# CAMERA_INTERFACE.net
KiCad netlist of a schematic drawn in Altium Designer
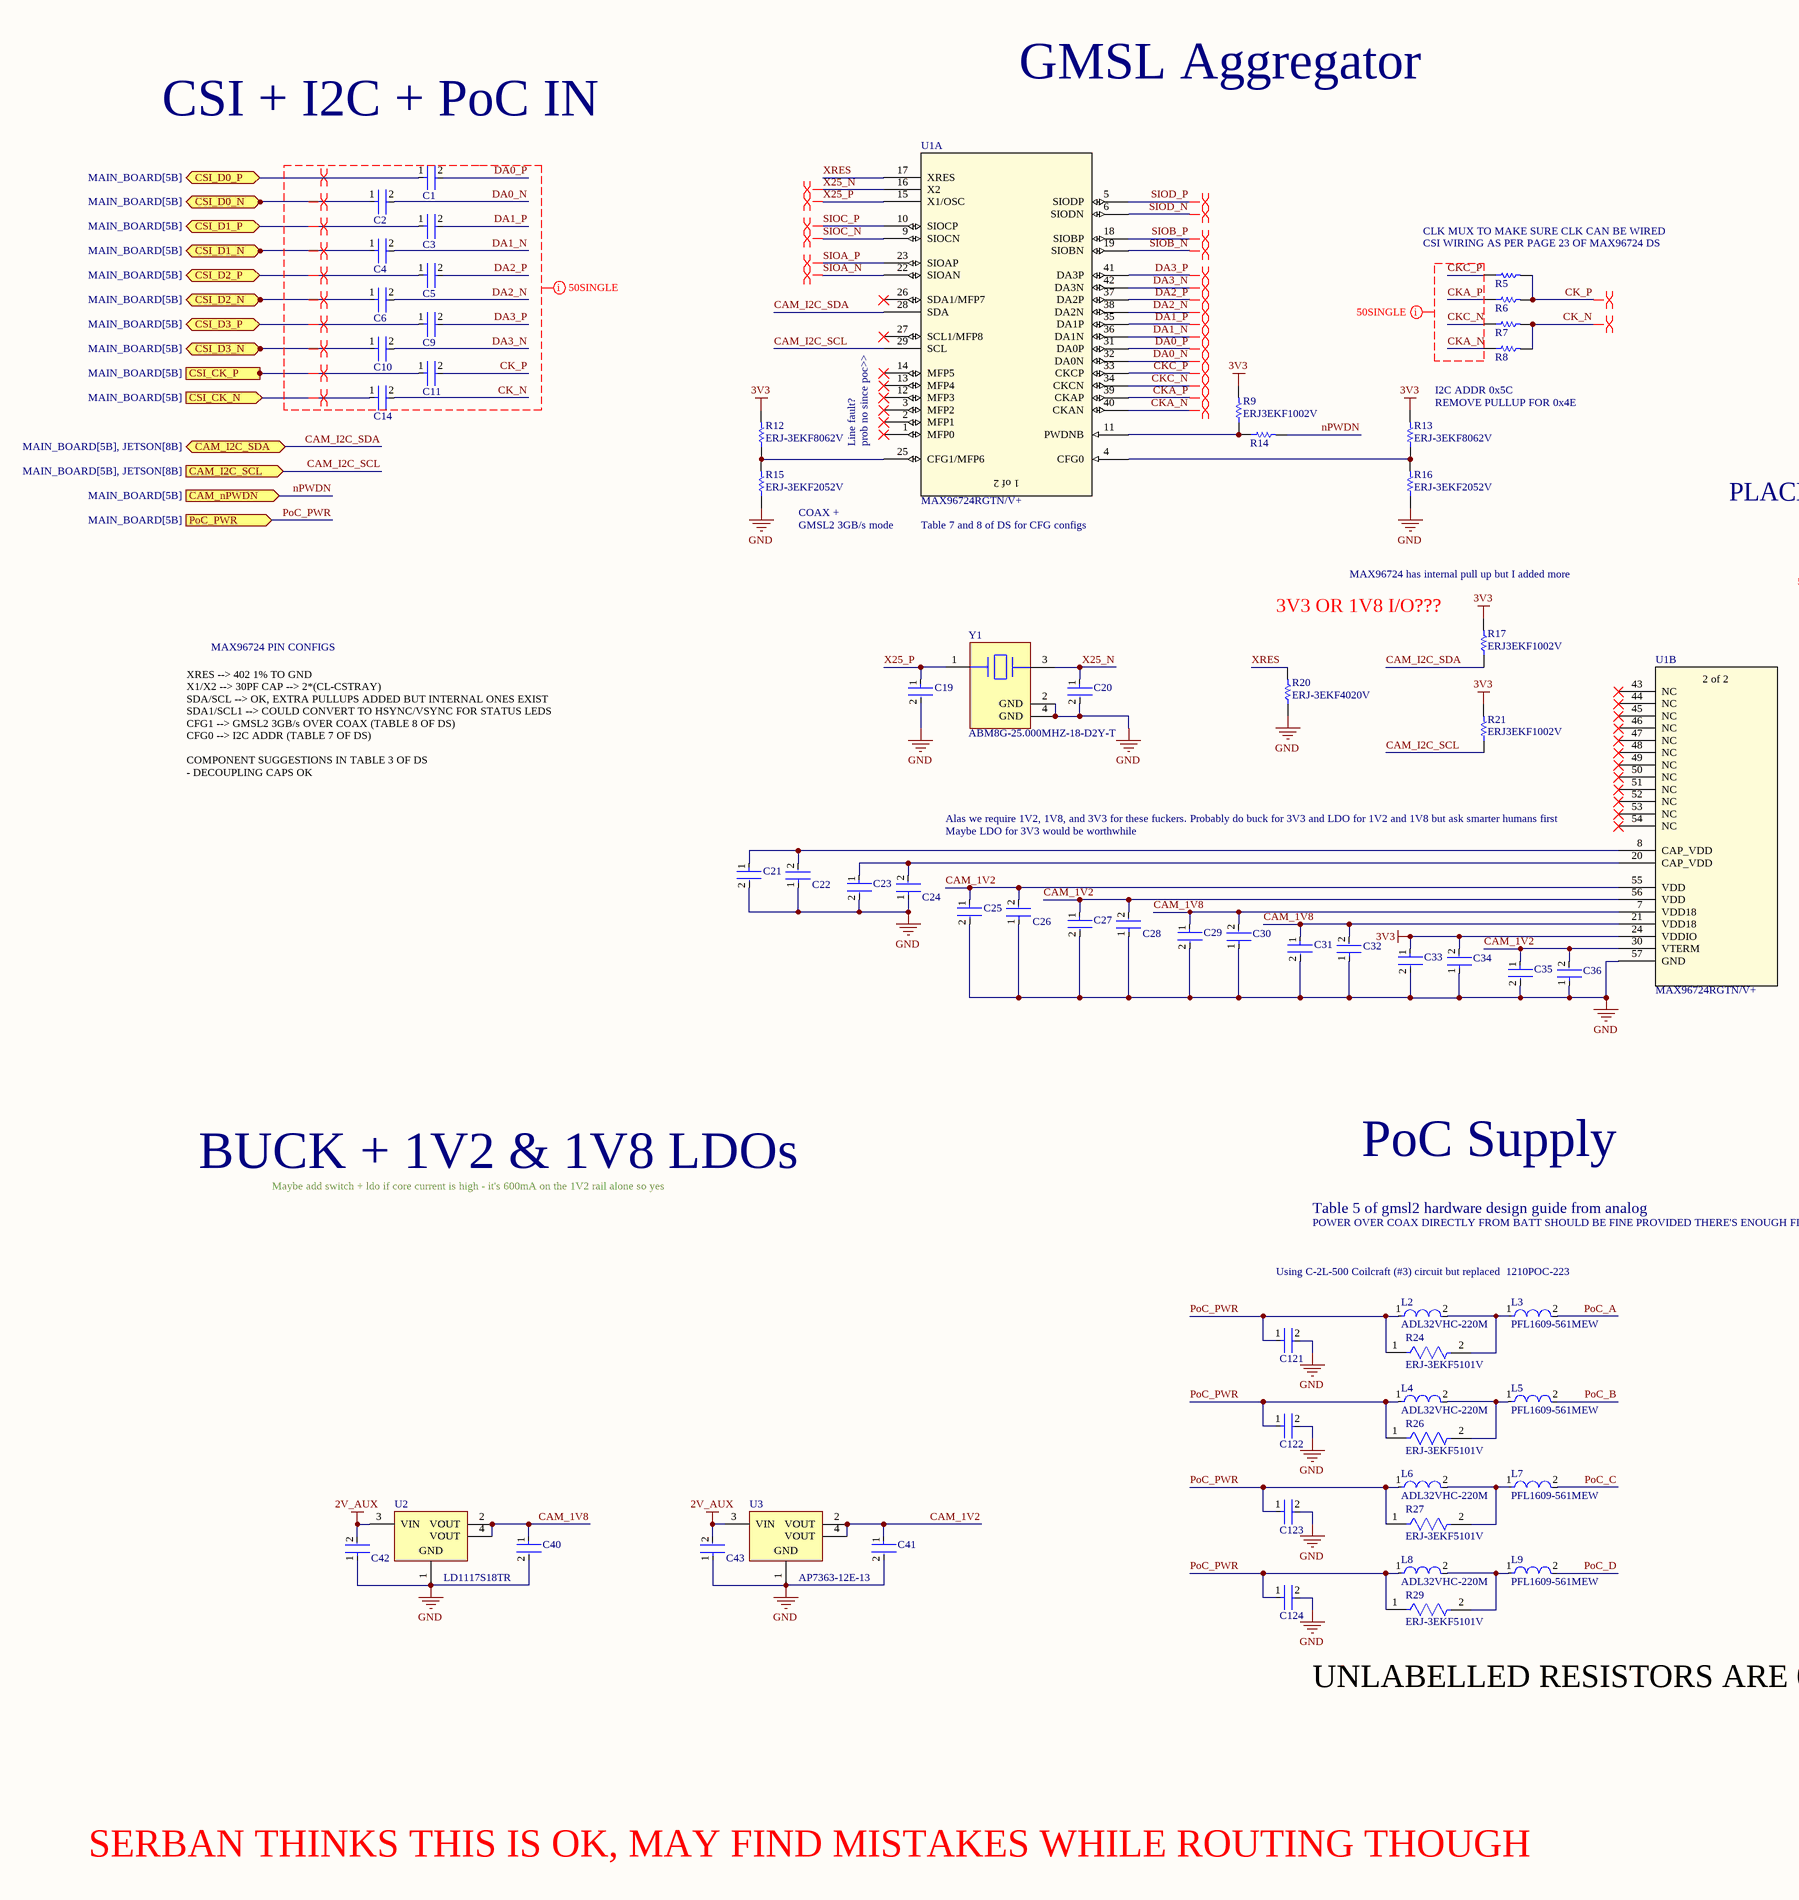
[diagram p0: CAMERA_INTERFACE.SchDoc, left]
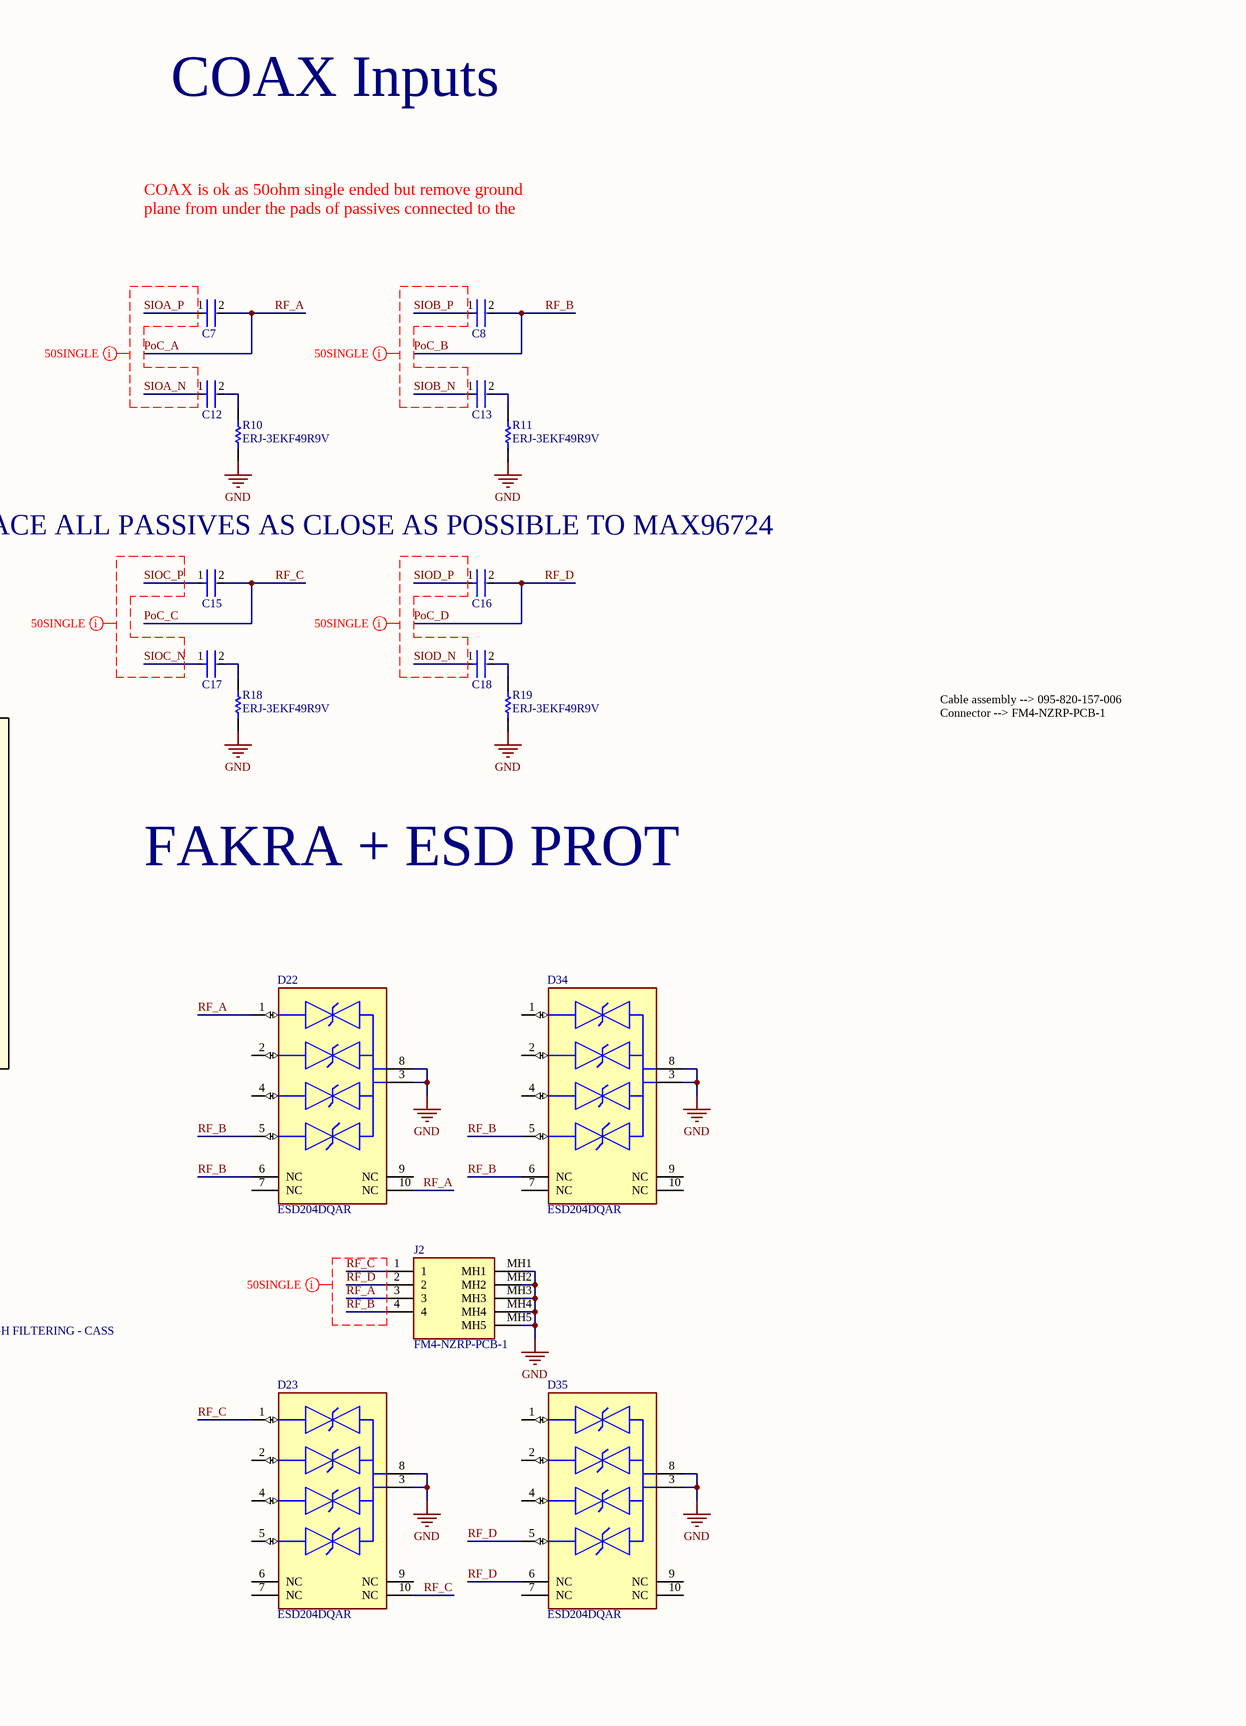
[diagram p1: CAMERA_INTERFACE.SchDoc, right]

(export (version "E")
  (design (tool "Eeschema 10.0.6"))
  (components
    (comp (ref "C1")
      (value "C1005X7R1H104K050BB")
      (footprint "FP-C1005-050-0_05-IPC_C")
      (description "Multilayer Ceramic Capacitors 100nF ±10% 50V X7R SMD 0402")
      (fields (field (name "VOLTAGE") "50V") (field (name "TOLERANCE") "10%"))
      (libsource (lib "Altium Content Vault") (part "b4654b650e69147ec39a6b967a45e02"))
    )
    (comp (ref "C2")
      (value "C1005X7R1H104K050BB")
      (footprint "FP-C1005-050-0_05-IPC_C")
      (description "Multilayer Ceramic Capacitors 100nF ±10% 50V X7R SMD 0402")
      (fields (field (name "VOLTAGE") "50V") (field (name "TOLERANCE") "10%"))
      (libsource (lib "Altium Content Vault") (part "b4654b650e69147ec39a6b967a45e02"))
    )
    (comp (ref "C3")
      (value "C1005X7R1H104K050BB")
      (footprint "FP-C1005-050-0_05-IPC_C")
      (description "Multilayer Ceramic Capacitors 100nF ±10% 50V X7R SMD 0402")
      (fields (field (name "VOLTAGE") "50V") (field (name "TOLERANCE") "10%"))
      (libsource (lib "Altium Content Vault") (part "b4654b650e69147ec39a6b967a45e02"))
    )
    (comp (ref "C4")
      (value "C1005X7R1H104K050BB")
      (footprint "FP-C1005-050-0_05-IPC_C")
      (description "Multilayer Ceramic Capacitors 100nF ±10% 50V X7R SMD 0402")
      (fields (field (name "VOLTAGE") "50V") (field (name "TOLERANCE") "10%"))
      (libsource (lib "Altium Content Vault") (part "b4654b650e69147ec39a6b967a45e02"))
    )
    (comp (ref "C5")
      (value "C1005X7R1H104K050BB")
      (footprint "FP-C1005-050-0_05-IPC_C")
      (description "Multilayer Ceramic Capacitors 100nF ±10% 50V X7R SMD 0402")
      (fields (field (name "VOLTAGE") "50V") (field (name "TOLERANCE") "10%"))
      (libsource (lib "Altium Content Vault") (part "b4654b650e69147ec39a6b967a45e02"))
    )
    (comp (ref "C6")
      (value "C1005X7R1H104K050BB")
      (footprint "FP-C1005-050-0_05-IPC_C")
      (description "Multilayer Ceramic Capacitors 100nF ±10% 50V X7R SMD 0402")
      (fields (field (name "VOLTAGE") "50V") (field (name "TOLERANCE") "10%"))
      (libsource (lib "Altium Content Vault") (part "b4654b650e69147ec39a6b967a45e02"))
    )
    (comp (ref "C7")
      (value "C1005X7R1H104K050BB")
      (footprint "FP-C1005-050-0_05-IPC_C")
      (description "Multilayer Ceramic Capacitors 100nF ±10% 50V X7R SMD 0402")
      (fields (field (name "VOLTAGE") "50V") (field (name "TOLERANCE") "10%"))
      (libsource (lib "Altium Content Vault") (part "b4654b650e69147ec39a6b967a45e02"))
    )
    (comp (ref "C8")
      (value "C1005X7R1H104K050BB")
      (footprint "FP-C1005-050-0_05-IPC_C")
      (description "Multilayer Ceramic Capacitors 100nF ±10% 50V X7R SMD 0402")
      (fields (field (name "VOLTAGE") "50V") (field (name "TOLERANCE") "10%"))
      (libsource (lib "Altium Content Vault") (part "b4654b650e69147ec39a6b967a45e02"))
    )
    (comp (ref "C9")
      (value "C1005X7R1H104K050BB")
      (footprint "FP-C1005-050-0_05-IPC_C")
      (description "Multilayer Ceramic Capacitors 100nF ±10% 50V X7R SMD 0402")
      (fields (field (name "VOLTAGE") "50V") (field (name "TOLERANCE") "10%"))
      (libsource (lib "Altium Content Vault") (part "b4654b650e69147ec39a6b967a45e02"))
    )
    (comp (ref "C10")
      (value "C1005X7R1H104K050BB")
      (footprint "FP-C1005-050-0_05-IPC_C")
      (description "Multilayer Ceramic Capacitors 100nF ±10% 50V X7R SMD 0402")
      (fields (field (name "VOLTAGE") "50V") (field (name "TOLERANCE") "10%"))
      (libsource (lib "Altium Content Vault") (part "b4654b650e69147ec39a6b967a45e02"))
    )
    (comp (ref "C11")
      (value "C1005X7R1H104K050BB")
      (footprint "FP-C1005-050-0_05-IPC_C")
      (description "Multilayer Ceramic Capacitors 100nF ±10% 50V X7R SMD 0402")
      (fields (field (name "VOLTAGE") "50V") (field (name "TOLERANCE") "10%"))
      (libsource (lib "Altium Content Vault") (part "b4654b650e69147ec39a6b967a45e02"))
    )
    (comp (ref "C12")
      (value "C1005X7R1H104K050BB")
      (footprint "FP-C1005-050-0_05-IPC_C")
      (description "Multilayer Ceramic Capacitors 100nF ±10% 50V X7R SMD 0402")
      (fields (field (name "VOLTAGE") "50V") (field (name "TOLERANCE") "10%"))
      (libsource (lib "Altium Content Vault") (part "b4654b650e69147ec39a6b967a45e02"))
    )
    (comp (ref "C13")
      (value "C1005X7R1H104K050BB")
      (footprint "FP-C1005-050-0_05-IPC_C")
      (description "Multilayer Ceramic Capacitors 100nF ±10% 50V X7R SMD 0402")
      (fields (field (name "VOLTAGE") "50V") (field (name "TOLERANCE") "10%"))
      (libsource (lib "Altium Content Vault") (part "b4654b650e69147ec39a6b967a45e02"))
    )
    (comp (ref "C14")
      (value "C1005X7R1H104K050BB")
      (footprint "FP-C1005-050-0_05-IPC_C")
      (description "Multilayer Ceramic Capacitors 100nF ±10% 50V X7R SMD 0402")
      (fields (field (name "VOLTAGE") "50V") (field (name "TOLERANCE") "10%"))
      (libsource (lib "Altium Content Vault") (part "b4654b650e69147ec39a6b967a45e02"))
    )
    (comp (ref "C15")
      (value "C1005X7R1H104K050BB")
      (footprint "FP-C1005-050-0_05-IPC_C")
      (description "Multilayer Ceramic Capacitors 100nF ±10% 50V X7R SMD 0402")
      (fields (field (name "VOLTAGE") "50V") (field (name "TOLERANCE") "10%"))
      (libsource (lib "Altium Content Vault") (part "b4654b650e69147ec39a6b967a45e02"))
    )
    (comp (ref "C16")
      (value "C1005X7R1H104K050BB")
      (footprint "FP-C1005-050-0_05-IPC_C")
      (description "Multilayer Ceramic Capacitors 100nF ±10% 50V X7R SMD 0402")
      (fields (field (name "VOLTAGE") "50V") (field (name "TOLERANCE") "10%"))
      (libsource (lib "Altium Content Vault") (part "b4654b650e69147ec39a6b967a45e02"))
    )
    (comp (ref "C17")
      (value "C1005X7R1H104K050BB")
      (footprint "FP-C1005-050-0_05-IPC_C")
      (description "Multilayer Ceramic Capacitors 100nF ±10% 50V X7R SMD 0402")
      (fields (field (name "VOLTAGE") "50V") (field (name "TOLERANCE") "10%"))
      (libsource (lib "Altium Content Vault") (part "b4654b650e69147ec39a6b967a45e02"))
    )
    (comp (ref "C18")
      (value "C1005X7R1H104K050BB")
      (footprint "FP-C1005-050-0_05-IPC_C")
      (description "Multilayer Ceramic Capacitors 100nF ±10% 50V X7R SMD 0402")
      (fields (field (name "VOLTAGE") "50V") (field (name "TOLERANCE") "10%"))
      (libsource (lib "Altium Content Vault") (part "b4654b650e69147ec39a6b967a45e02"))
    )
    (comp (ref "C19")
      (value "C0603C300J5GACTU")
      (footprint "FP-C0603C-CF-MFG")
      (description "CAP CER 30PF 50V 5% NP0 0603")
      (fields
        (field (name "MANUFACTURER") "KEMET")
        (field (name "OCTOPART") "https://octopart.com/c0603c300j5gactu-kemet-199455")
      )
      (libsource (lib "Altium Content Vault") (part "b4654b650e69147ec39a6b967a45e02"))
    )
    (comp (ref "C20")
      (value "C0603C300J5GACTU")
      (footprint "FP-C0603C-CF-MFG")
      (description "CAP CER 30PF 50V 5% NP0 0603")
      (fields
        (field (name "MANUFACTURER") "KEMET")
        (field (name "OCTOPART") "https://octopart.com/c0603c300j5gactu-kemet-199455")
      )
      (libsource (lib "Altium Content Vault") (part "b4654b650e69147ec39a6b967a45e02"))
    )
    (comp (ref "C21")
      (value "CL05A106MP5NUNC")
      (footprint "FP-CL05A106MP5NUNC-MFG")
      (description "CAP CER 10UF 10V X5R 0402")
      (fields
        (field (name "OCTOPART") "https://octopart.com/cl05a106mp5nunc-samsung-22457395")
        (field (name "TOLERANCE") "20%")
      )
      (libsource (lib "Altium Content Vault") (part "b4654b650e69147ec39a6b967a45e02"))
    )
    (comp (ref "C22")
      (value "C1005X7R1H104K050BB")
      (footprint "FP-C1005-050-0_05-IPC_C")
      (description "Multilayer Ceramic Capacitors 100nF ±10% 50V X7R SMD 0402")
      (fields (field (name "VOLTAGE") "50V") (field (name "TOLERANCE") "10%"))
      (libsource (lib "Altium Content Vault") (part "b4654b650e69147ec39a6b967a45e02"))
    )
    (comp (ref "C23")
      (value "CL05A106MP5NUNC")
      (footprint "FP-CL05A106MP5NUNC-MFG")
      (description "CAP CER 10UF 10V X5R 0402")
      (fields
        (field (name "OCTOPART") "https://octopart.com/cl05a106mp5nunc-samsung-22457395")
        (field (name "TOLERANCE") "20%")
      )
      (libsource (lib "Altium Content Vault") (part "b4654b650e69147ec39a6b967a45e02"))
    )
    (comp (ref "C24")
      (value "C1005X7R1H104K050BB")
      (footprint "FP-C1005-050-0_05-IPC_C")
      (description "Multilayer Ceramic Capacitors 100nF ±10% 50V X7R SMD 0402")
      (fields (field (name "VOLTAGE") "50V") (field (name "TOLERANCE") "10%"))
      (libsource (lib "Altium Content Vault") (part "b4654b650e69147ec39a6b967a45e02"))
    )
    (comp (ref "C25")
      (value "CL05A106MP5NUNC")
      (footprint "FP-CL05A106MP5NUNC-MFG")
      (description "CAP CER 10UF 10V X5R 0402")
      (fields
        (field (name "OCTOPART") "https://octopart.com/cl05a106mp5nunc-samsung-22457395")
        (field (name "TOLERANCE") "20%")
      )
      (libsource (lib "Altium Content Vault") (part "b4654b650e69147ec39a6b967a45e02"))
    )
    (comp (ref "C26")
      (value "C1005X7R1H104K050BB")
      (footprint "FP-C1005-050-0_05-IPC_C")
      (description "Multilayer Ceramic Capacitors 100nF ±10% 50V X7R SMD 0402")
      (fields (field (name "VOLTAGE") "50V") (field (name "TOLERANCE") "10%"))
      (libsource (lib "Altium Content Vault") (part "b4654b650e69147ec39a6b967a45e02"))
    )
    (comp (ref "C27")
      (value "CL05A106MP5NUNC")
      (footprint "FP-CL05A106MP5NUNC-MFG")
      (description "CAP CER 10UF 10V X5R 0402")
      (fields
        (field (name "OCTOPART") "https://octopart.com/cl05a106mp5nunc-samsung-22457395")
        (field (name "TOLERANCE") "20%")
      )
      (libsource (lib "Altium Content Vault") (part "b4654b650e69147ec39a6b967a45e02"))
    )
    (comp (ref "C28")
      (value "C1005X7R1H104K050BB")
      (footprint "FP-C1005-050-0_05-IPC_C")
      (description "Multilayer Ceramic Capacitors 100nF ±10% 50V X7R SMD 0402")
      (fields (field (name "VOLTAGE") "50V") (field (name "TOLERANCE") "10%"))
      (libsource (lib "Altium Content Vault") (part "b4654b650e69147ec39a6b967a45e02"))
    )
    (comp (ref "C29")
      (value "CL05A106MP5NUNC")
      (footprint "FP-CL05A106MP5NUNC-MFG")
      (description "CAP CER 10UF 10V X5R 0402")
      (fields
        (field (name "OCTOPART") "https://octopart.com/cl05a106mp5nunc-samsung-22457395")
        (field (name "TOLERANCE") "20%")
      )
      (libsource (lib "Altium Content Vault") (part "b4654b650e69147ec39a6b967a45e02"))
    )
    (comp (ref "C30")
      (value "C0402C103M5RACTU")
      (footprint "FP-C0402-BB-MFG")
      (description "CAP CER 10000PF 50V 20% X7R 0402")
      (fields
        (field (name "TOLERANCE") "0.2")
        (field (name "OCTOPART") "https://octopart.com/c0402c103m5ractu-kemet-17125571")
      )
      (libsource (lib "Altium Content Vault") (part "b4654b650e69147ec39a6b967a45e02"))
    )
    (comp (ref "C31")
      (value "CL05A106MP5NUNC")
      (footprint "FP-CL05A106MP5NUNC-MFG")
      (description "CAP CER 10UF 10V X5R 0402")
      (fields
        (field (name "OCTOPART") "https://octopart.com/cl05a106mp5nunc-samsung-22457395")
        (field (name "TOLERANCE") "20%")
      )
      (libsource (lib "Altium Content Vault") (part "b4654b650e69147ec39a6b967a45e02"))
    )
    (comp (ref "C32")
      (value "C0402C103M5RACTU")
      (footprint "FP-C0402-BB-MFG")
      (description "CAP CER 10000PF 50V 20% X7R 0402")
      (fields
        (field (name "TOLERANCE") "0.2")
        (field (name "OCTOPART") "https://octopart.com/c0402c103m5ractu-kemet-17125571")
      )
      (libsource (lib "Altium Content Vault") (part "b4654b650e69147ec39a6b967a45e02"))
    )
    (comp (ref "C33")
      (value "CL05A106MP5NUNC")
      (footprint "FP-CL05A106MP5NUNC-MFG")
      (description "CAP CER 10UF 10V X5R 0402")
      (fields
        (field (name "OCTOPART") "https://octopart.com/cl05a106mp5nunc-samsung-22457395")
        (field (name "TOLERANCE") "20%")
      )
      (libsource (lib "Altium Content Vault") (part "b4654b650e69147ec39a6b967a45e02"))
    )
    (comp (ref "C34")
      (value "C0402C103M5RACTU")
      (footprint "FP-C0402-BB-MFG")
      (description "CAP CER 10000PF 50V 20% X7R 0402")
      (fields
        (field (name "TOLERANCE") "0.2")
        (field (name "OCTOPART") "https://octopart.com/c0402c103m5ractu-kemet-17125571")
      )
      (libsource (lib "Altium Content Vault") (part "b4654b650e69147ec39a6b967a45e02"))
    )
    (comp (ref "C35")
      (value "CL05A106MP5NUNC")
      (footprint "FP-CL05A106MP5NUNC-MFG")
      (description "CAP CER 10UF 10V X5R 0402")
      (fields
        (field (name "OCTOPART") "https://octopart.com/cl05a106mp5nunc-samsung-22457395")
        (field (name "TOLERANCE") "20%")
      )
      (libsource (lib "Altium Content Vault") (part "b4654b650e69147ec39a6b967a45e02"))
    )
    (comp (ref "C36")
      (value "C0402C103M5RACTU")
      (footprint "FP-C0402-BB-MFG")
      (description "CAP CER 10000PF 50V 20% X7R 0402")
      (fields
        (field (name "TOLERANCE") "0.2")
        (field (name "OCTOPART") "https://octopart.com/c0402c103m5ractu-kemet-17125571")
      )
      (libsource (lib "Altium Content Vault") (part "b4654b650e69147ec39a6b967a45e02"))
    )
    (comp (ref "C40")
      (value "GRM188R60J106ME47D")
      (footprint "FP-GRM188-0_1-e0_2_0_55-IPC_A")
      (description "Chip Multilayer Ceramic Capacitors for General Purpose, 0603, 10uF, X5R, 15%, 20%, 6.3V")
      (fields (field (name "VOLTAGE") "6.3V") (field (name "TOLERANCE") "20%"))
      (libsource (lib "Altium Content Vault") (part "02cd4be3c70576c341d710602a673aa"))
    )
    (comp (ref "C41")
      (value "GRM188R60J106ME47D")
      (footprint "FP-GRM188-0_1-e0_2_0_55-IPC_A")
      (description "Chip Multilayer Ceramic Capacitors for General Purpose, 0603, 10uF, X5R, 15%, 20%, 6.3V")
      (fields (field (name "VOLTAGE") "6.3V") (field (name "TOLERANCE") "20%"))
      (libsource (lib "Altium Content Vault") (part "02cd4be3c70576c341d710602a673aa"))
    )
    (comp (ref "C42")
      (value "C1005X7R1H104K050BB")
      (footprint "FP-C1005-050-0_05-IPC_C")
      (description "Multilayer Ceramic Capacitors 100nF ±10% 50V X7R SMD 0402")
      (fields (field (name "VOLTAGE") "50V") (field (name "TOLERANCE") "10%"))
      (libsource (lib "Altium Content Vault") (part "b4654b650e69147ec39a6b967a45e02"))
    )
    (comp (ref "C43")
      (value "C1005X7R1H104K050BB")
      (footprint "FP-C1005-050-0_05-IPC_C")
      (description "Multilayer Ceramic Capacitors 100nF ±10% 50V X7R SMD 0402")
      (fields (field (name "VOLTAGE") "50V") (field (name "TOLERANCE") "10%"))
      (libsource (lib "Altium Content Vault") (part "b4654b650e69147ec39a6b967a45e02"))
    )
    (comp (ref "C121")
      (value "GRM21BR61E226ME44L")
      (footprint "FP-GRM21B-0_2-e0_2_0_7-IPC_B")
      (description "Chip Multilayer Ceramic Capacitors for General Purpose, 0805, 22uF, X5R, 15%, 20%, 25V")
      (fields (field (name "TOLERANCE") "20%") (field (name "VOLTAGE") "25V"))
      (libsource (lib "Altium Content Vault") (part "b4654b650e69147ec39a6b967a45e02"))
    )
    (comp (ref "C122")
      (value "GRM21BR61E226ME44L")
      (footprint "FP-GRM21B-0_2-e0_2_0_7-IPC_B")
      (description "Chip Multilayer Ceramic Capacitors for General Purpose, 0805, 22uF, X5R, 15%, 20%, 25V")
      (fields (field (name "TOLERANCE") "20%") (field (name "VOLTAGE") "25V"))
      (libsource (lib "Altium Content Vault") (part "b4654b650e69147ec39a6b967a45e02"))
    )
    (comp (ref "C123")
      (value "GRM21BR61E226ME44L")
      (footprint "FP-GRM21B-0_2-e0_2_0_7-IPC_B")
      (description "Chip Multilayer Ceramic Capacitors for General Purpose, 0805, 22uF, X5R, 15%, 20%, 25V")
      (fields (field (name "TOLERANCE") "20%") (field (name "VOLTAGE") "25V"))
      (libsource (lib "Altium Content Vault") (part "b4654b650e69147ec39a6b967a45e02"))
    )
    (comp (ref "C124")
      (value "GRM21BR61E226ME44L")
      (footprint "FP-GRM21B-0_2-e0_2_0_7-IPC_B")
      (description "Chip Multilayer Ceramic Capacitors for General Purpose, 0805, 22uF, X5R, 15%, 20%, 25V")
      (fields (field (name "TOLERANCE") "20%") (field (name "VOLTAGE") "25V"))
      (libsource (lib "Altium Content Vault") (part "b4654b650e69147ec39a6b967a45e02"))
    )
    (comp (ref "D22")
      (value "ESD204DQAR")
      (footprint "FP-DQA0010A-MFG")
      (description "4-CHANNEL LOW-CAPACITANCE SURGE")
      (fields
        (field (name "MANUFACTURER") "Texas Instruments")
        (field (name "OCTOPART") "https://octopart.com/esd204dqar-texas+instruments-89917476")
      )
      (libsource (lib "Altium Content Vault") (part "1465e58c1818c7767b55926832f0bf5"))
    )
    (comp (ref "D23")
      (value "ESD204DQAR")
      (footprint "FP-DQA0010A-MFG")
      (description "4-CHANNEL LOW-CAPACITANCE SURGE")
      (fields
        (field (name "MANUFACTURER") "Texas Instruments")
        (field (name "OCTOPART") "https://octopart.com/esd204dqar-texas+instruments-89917476")
      )
      (libsource (lib "Altium Content Vault") (part "1465e58c1818c7767b55926832f0bf5"))
    )
    (comp (ref "D34")
      (value "ESD204DQAR")
      (footprint "FP-DQA0010A-MFG")
      (description "4-CHANNEL LOW-CAPACITANCE SURGE")
      (fields
        (field (name "MANUFACTURER") "Texas Instruments")
        (field (name "OCTOPART") "https://octopart.com/esd204dqar-texas+instruments-89917476")
      )
      (libsource (lib "Altium Content Vault") (part "1465e58c1818c7767b55926832f0bf5"))
    )
    (comp (ref "D35")
      (value "ESD204DQAR")
      (footprint "FP-DQA0010A-MFG")
      (description "4-CHANNEL LOW-CAPACITANCE SURGE")
      (fields
        (field (name "MANUFACTURER") "Texas Instruments")
        (field (name "OCTOPART") "https://octopart.com/esd204dqar-texas+instruments-89917476")
      )
      (libsource (lib "Altium Content Vault") (part "1465e58c1818c7767b55926832f0bf5"))
    )
    (comp (ref "J2")
      (value "FM4-NZRP-PCB-1")
      (footprint "FM4-NZRP-PCB-1-Footprint-1")
      (description "Connector RF Mini-FAKRA Plug 9GHz 50Ohm Solder Right Angle Through Hole")
      (libsource (lib "uORocketry Hardware") (part "FM4-NZRP-PCB-1"))
    )
    (comp (ref "L2")
      (value "ADL32VHC-220M")
      (footprint "FP-1210POC-MFG")
      (description "NOT COILCRAFT - ACTUAL P# --> ADL32VHC-220M\r\n - Power Injection Chokes for PoC")
      (fields
        (field (name "MANUFACTURER") "coilcraft")
        (field (name "OCTOPART") "https://octopart.com/1210poc-223mrc-coilcraft-103207315")
      )
      (libsource (lib "Altium Content Vault") (part "725321dda6339637d4d059423bc1c3c"))
    )
    (comp (ref "L3")
      (value "PFL1609-561MEW")
      (footprint "FP-PFL1609-MFG")
      (description "Fixed Inductors PFL1609 Low Profile 0.56 uH 20 % 1.4 A")
      (fields (field (name "MANUFACTURER") "coilcraft") (field (name "TOLERANCE") "20%"))
      (libsource (lib "Altium Content Vault") (part "725321dda6339637d4d059423bc1c3c"))
    )
    (comp (ref "L4")
      (value "ADL32VHC-220M")
      (footprint "FP-1210POC-MFG")
      (description "NOT COILCRAFT - ACTUAL P# --> ADL32VHC-220M\r\n - Power Injection Chokes for PoC")
      (fields
        (field (name "MANUFACTURER") "coilcraft")
        (field (name "OCTOPART") "https://octopart.com/1210poc-223mrc-coilcraft-103207315")
      )
      (libsource (lib "Altium Content Vault") (part "725321dda6339637d4d059423bc1c3c"))
    )
    (comp (ref "L5")
      (value "PFL1609-561MEW")
      (footprint "FP-PFL1609-MFG")
      (description "Fixed Inductors PFL1609 Low Profile 0.56 uH 20 % 1.4 A")
      (fields (field (name "MANUFACTURER") "coilcraft") (field (name "TOLERANCE") "20%"))
      (libsource (lib "Altium Content Vault") (part "725321dda6339637d4d059423bc1c3c"))
    )
    (comp (ref "L6")
      (value "ADL32VHC-220M")
      (footprint "FP-1210POC-MFG")
      (description "NOT COILCRAFT - ACTUAL P# --> ADL32VHC-220M\r\n - Power Injection Chokes for PoC")
      (fields
        (field (name "MANUFACTURER") "coilcraft")
        (field (name "OCTOPART") "https://octopart.com/1210poc-223mrc-coilcraft-103207315")
      )
      (libsource (lib "Altium Content Vault") (part "725321dda6339637d4d059423bc1c3c"))
    )
    (comp (ref "L7")
      (value "PFL1609-561MEW")
      (footprint "FP-PFL1609-MFG")
      (description "Fixed Inductors PFL1609 Low Profile 0.56 uH 20 % 1.4 A")
      (fields (field (name "MANUFACTURER") "coilcraft") (field (name "TOLERANCE") "20%"))
      (libsource (lib "Altium Content Vault") (part "725321dda6339637d4d059423bc1c3c"))
    )
    (comp (ref "L8")
      (value "ADL32VHC-220M")
      (footprint "FP-1210POC-MFG")
      (description "NOT COILCRAFT - ACTUAL P# --> ADL32VHC-220M\r\n - Power Injection Chokes for PoC")
      (fields
        (field (name "MANUFACTURER") "coilcraft")
        (field (name "OCTOPART") "https://octopart.com/1210poc-223mrc-coilcraft-103207315")
      )
      (libsource (lib "Altium Content Vault") (part "725321dda6339637d4d059423bc1c3c"))
    )
    (comp (ref "L9")
      (value "PFL1609-561MEW")
      (footprint "FP-PFL1609-MFG")
      (description "Fixed Inductors PFL1609 Low Profile 0.56 uH 20 % 1.4 A")
      (fields (field (name "MANUFACTURER") "coilcraft") (field (name "TOLERANCE") "20%"))
      (libsource (lib "Altium Content Vault") (part "725321dda6339637d4d059423bc1c3c"))
    )
    (comp (ref "R5")
      (value "0402 JUMPER 0 OHM")
      (footprint "RESC1005X40X25NL05T05")
      (description "READ THE NAME")
      (libsource (lib "uORocketry Hardware") (part "RES"))
    )
    (comp (ref "R6")
      (value "0402 JUMPER 0 OHM")
      (footprint "RESC1005X40X25NL05T05")
      (description "READ THE NAME")
      (libsource (lib "uORocketry Hardware") (part "RES"))
    )
    (comp (ref "R7")
      (value "0402 JUMPER 0 OHM")
      (footprint "RESC1005X40X25NL05T05")
      (description "READ THE NAME")
      (libsource (lib "uORocketry Hardware") (part "RES"))
    )
    (comp (ref "R8")
      (value "0402 JUMPER 0 OHM")
      (footprint "RESC1005X40X25NL05T05")
      (description "READ THE NAME")
      (libsource (lib "uORocketry Hardware") (part "RES"))
    )
    (comp (ref "R9")
      (value "ERJ3EKF1002V")
      (footprint "RESC1609X55X30LL15T15")
      (description "Chip Resistor, 10 KOhm, +/- 1%, 0.1 W, -55 to 155 degC, 0603 (1608 Metric), RoHS, Tape and Reel")
      (fields (field (name "TOLERANCE") "1%") (field (name "MANUFACTURER") "Panasonic"))
      (libsource (lib "Altium Content Vault") (part "RES-2"))
    )
    (comp (ref "R10")
      (value "ERJ-3EKF49R9V")
      (footprint "RESC1608X55X30ML15T15")
      (fields (field (name "MANUFACTURER") "Panasonic"))
      (libsource (lib "Altium Content Vault") (part "RES"))
    )
    (comp (ref "R11")
      (value "ERJ-3EKF49R9V")
      (footprint "RESC1608X55X30ML15T15")
      (fields (field (name "MANUFACTURER") "Panasonic"))
      (libsource (lib "Altium Content Vault") (part "RES"))
    )
    (comp (ref "R12")
      (value "ERJ-3EKF8062V")
      (footprint "RESC1608X55X30LL15T15")
      (fields (field (name "MANUFACTURER") "Panasonic"))
      (libsource (lib "Altium Content Vault") (part "RES"))
    )
    (comp (ref "R13")
      (value "ERJ-3EKF8062V")
      (footprint "RESC1608X55X30LL15T15")
      (fields (field (name "MANUFACTURER") "Panasonic"))
      (libsource (lib "Altium Content Vault") (part "RES"))
    )
    (comp (ref "R14")
      (value "0402 JUMPER 0 OHM")
      (footprint "RESC1005X40X25NL05T05")
      (description "READ THE NAME")
      (libsource (lib "uORocketry Hardware") (part "RES"))
    )
    (comp (ref "R15")
      (value "ERJ-3EKF2052V")
      (footprint "RESC1608X55X30NL15T15")
      (fields (field (name "MANUFACTURER") "Panasonic"))
      (libsource (lib "Altium Content Vault") (part "RES"))
    )
    (comp (ref "R16")
      (value "ERJ-3EKF2052V")
      (footprint "RESC1608X55X30NL15T15")
      (fields (field (name "MANUFACTURER") "Panasonic"))
      (libsource (lib "Altium Content Vault") (part "RES"))
    )
    (comp (ref "R17")
      (value "ERJ3EKF1002V")
      (footprint "RESC1609X55X30LL15T15")
      (description "Chip Resistor, 10 KOhm, +/- 1%, 0.1 W, -55 to 155 degC, 0603 (1608 Metric), RoHS, Tape and Reel")
      (fields (field (name "TOLERANCE") "1%") (field (name "MANUFACTURER") "Panasonic"))
      (libsource (lib "Altium Content Vault") (part "RES-2"))
    )
    (comp (ref "R18")
      (value "ERJ-3EKF49R9V")
      (footprint "RESC1608X55X30ML15T15")
      (fields (field (name "MANUFACTURER") "Panasonic"))
      (libsource (lib "Altium Content Vault") (part "RES"))
    )
    (comp (ref "R19")
      (value "ERJ-3EKF49R9V")
      (footprint "RESC1608X55X30ML15T15")
      (fields (field (name "MANUFACTURER") "Panasonic"))
      (libsource (lib "Altium Content Vault") (part "RES"))
    )
    (comp (ref "R20")
      (value "ERJ-3EKF4020V")
      (footprint "RESC1608X55X30LL15T15")
      (fields (field (name "MANUFACTURER") "Panasonic"))
      (libsource (lib "Altium Content Vault") (part "RES"))
    )
    (comp (ref "R21")
      (value "ERJ3EKF1002V")
      (footprint "RESC1609X55X30LL15T15")
      (description "Chip Resistor, 10 KOhm, +/- 1%, 0.1 W, -55 to 155 degC, 0603 (1608 Metric), RoHS, Tape and Reel")
      (fields (field (name "TOLERANCE") "1%") (field (name "MANUFACTURER") "Panasonic"))
      (libsource (lib "Altium Content Vault") (part "RES-2"))
    )
    (comp (ref "R24")
      (value "ERJ-3EKF5101V")
      (footprint "FP-ERJ3EK-MFG")
      (description "RES SMD 5.1K OHM 1% 1/10W 0603")
      (fields (field (name "TOLERANCE") "1%"))
      (libsource (lib "Altium Content Vault") (part "1029c3af85768c4190bb7ad29bc67b5"))
    )
    (comp (ref "R26")
      (value "ERJ-3EKF5101V")
      (footprint "FP-ERJ3EK-MFG")
      (description "RES SMD 5.1K OHM 1% 1/10W 0603")
      (fields (field (name "TOLERANCE") "1%"))
      (libsource (lib "Altium Content Vault") (part "1029c3af85768c4190bb7ad29bc67b5"))
    )
    (comp (ref "R27")
      (value "ERJ-3EKF5101V")
      (footprint "FP-ERJ3EK-MFG")
      (description "RES SMD 5.1K OHM 1% 1/10W 0603")
      (fields (field (name "TOLERANCE") "1%"))
      (libsource (lib "Altium Content Vault") (part "1029c3af85768c4190bb7ad29bc67b5"))
    )
    (comp (ref "R29")
      (value "ERJ-3EKF5101V")
      (footprint "FP-ERJ3EK-MFG")
      (description "RES SMD 5.1K OHM 1% 1/10W 0603")
      (fields (field (name "TOLERANCE") "1%"))
      (libsource (lib "Altium Content Vault") (part "1029c3af85768c4190bb7ad29bc67b5"))
    )
    (comp (ref "U1")
      (value "MAX96724RGTN/V+")
      (footprint "QFN50P800X800X80_HS-57N")
      (description "Quad Tunneling GMSL2/1 to CSI-2 Deserializer")
      (libsource (lib "") (part "MAX96724RGTN_V+-Symbol-1_1"))
    )
    (comp (ref "U2")
      (value "LD1117S18TR")
      (footprint "SOT-223_M")
      (description "Fixed Low Drop Positive Voltage Regulator, 1.8V, 4-Pin SOT-223, Tape and Reel")
      (libsource (lib "Altium Content Vault") (part "PM-REG-LD1117-SOT4"))
    )
    (comp (ref "U3")
      (value "AP7363-12E-13")
      (footprint "SOT-223_M")
      (description "Fixed Low Drop Positive Voltage Regulator, 1.2V (pn is for 1.5A LDO), 4-Pin SOT-223, Tape and Reel")
      (libsource (lib "Altium Content Vault") (part "PM-REG-LD1117-SOT4"))
    )
    (comp (ref "Y1")
      (value "ABM8G-25.000MHZ-18-D2Y-T")
      (footprint "FP-ABM8G-MFG")
      (description "Crystal 25MHz ±20ppm (Tol) ±30ppm (Stability) 18pF FUND 60Ω 4-Pin SMD T/R")
      (fields (field (name "TOLERANCE") "20ppm"))
      (libsource (lib "Altium Content Vault") (part "48e526d86b7f2615d98721063c72f49"))
    )
  )
  (nets
    (net (code "1") (name "/CAM_1V2") (class "Default")
      (node (ref "C25") (pin "1") (pinfunction "1_1") (pintype "passive"))
      (node (ref "C26") (pin "2") (pinfunction "2_2") (pintype "passive"))
      (node (ref "C27") (pin "1") (pinfunction "1_1") (pintype "passive"))
      (node (ref "C28") (pin "2") (pinfunction "2_2") (pintype "passive"))
      (node (ref "C35") (pin "1") (pinfunction "1_1") (pintype "passive"))
      (node (ref "C36") (pin "2") (pinfunction "2_2") (pintype "passive"))
      (node (ref "C41") (pin "1") (pinfunction "1_1") (pintype "passive"))
      (node (ref "U1") (pin "30") (pinfunction "VTERM_30") (pintype "power_in"))
      (node (ref "U1") (pin "55") (pinfunction "VDD_55") (pintype "power_in"))
      (node (ref "U1") (pin "56") (pinfunction "VDD_56") (pintype "power_in"))
      (node (ref "U3") (pin "2") (pinfunction "VOUT_2") (pintype "power_in"))
      (node (ref "U3") (pin "4") (pinfunction "VOUT_4") (pintype "power_in"))
    )
    (net (code "2") (name "/CAM_1V8") (class "Default")
      (node (ref "C29") (pin "1") (pinfunction "1_1") (pintype "passive"))
      (node (ref "C30") (pin "2") (pinfunction "2_2") (pintype "passive"))
      (node (ref "C31") (pin "1") (pinfunction "1_1") (pintype "passive"))
      (node (ref "C32") (pin "2") (pinfunction "2_2") (pintype "passive"))
      (node (ref "C40") (pin "1") (pinfunction "1_1") (pintype "passive"))
      (node (ref "U1") (pin "21") (pinfunction "VDD18_21") (pintype "power_in"))
      (node (ref "U1") (pin "7") (pinfunction "VDD18_7") (pintype "power_in"))
      (node (ref "U2") (pin "2") (pinfunction "VOUT_2") (pintype "power_in"))
      (node (ref "U2") (pin "4") (pinfunction "VOUT_4") (pintype "power_in"))
    )
    (net (code "3") (name "/CAM_I2C_SCL") (class "Default")
      (node (ref "R21") (pin "1") (pinfunction "1_1") (pintype "passive"))
      (node (ref "U1") (pin "29") (pinfunction "SCL_29") (pintype "passive"))
    )
    (net (code "4") (name "/CAM_I2C_SDA") (class "Default")
      (node (ref "R17") (pin "1") (pinfunction "1_1") (pintype "passive"))
      (node (ref "U1") (pin "28") (pinfunction "SDA_28") (pintype "passive"))
    )
    (net (code "5") (name "/CKA_N") (class "Default")
      (node (ref "R8") (pin "1") (pinfunction "1_1") (pintype "passive"))
      (node (ref "U1") (pin "40") (pinfunction "CKAN_40") (pintype "bidirectional"))
    )
    (net (code "6") (name "/CKA_P") (class "Default")
      (node (ref "R6") (pin "1") (pinfunction "1_1") (pintype "passive"))
      (node (ref "U1") (pin "39") (pinfunction "CKAP_39") (pintype "bidirectional"))
    )
    (net (code "7") (name "/CKC_N") (class "Default")
      (node (ref "R7") (pin "1") (pinfunction "1_1") (pintype "passive"))
      (node (ref "U1") (pin "34") (pinfunction "CKCN_34") (pintype "bidirectional"))
    )
    (net (code "8") (name "/CKC_P") (class "Default")
      (node (ref "R5") (pin "1") (pinfunction "1_1") (pintype "passive"))
      (node (ref "U1") (pin "33") (pinfunction "CKCP_33") (pintype "bidirectional"))
    )
    (net (code "9") (name "/CK_N") (class "Default")
      (node (ref "C14") (pin "2") (pinfunction "2_2") (pintype "passive"))
      (node (ref "R7") (pin "2") (pinfunction "2_2") (pintype "passive"))
      (node (ref "R8") (pin "2") (pinfunction "2_2") (pintype "passive"))
    )
    (net (code "10") (name "/CK_P") (class "Default")
      (node (ref "C11") (pin "2") (pinfunction "2_2") (pintype "passive"))
      (node (ref "R5") (pin "2") (pinfunction "2_2") (pintype "passive"))
      (node (ref "R6") (pin "2") (pinfunction "2_2") (pintype "passive"))
    )
    (net (code "11") (name "/CSI_CK_N") (class "Default")
      (node (ref "C14") (pin "1") (pinfunction "1_1") (pintype "passive"))
    )
    (net (code "12") (name "/CSI_CK_P") (class "Default")
      (node (ref "C11") (pin "1") (pinfunction "1_1") (pintype "passive"))
    )
    (net (code "13") (name "/CSI_D0_N") (class "Default")
      (node (ref "C2") (pin "1") (pinfunction "1_1") (pintype "passive"))
    )
    (net (code "14") (name "/CSI_D0_P") (class "Default")
      (node (ref "C1") (pin "1") (pinfunction "1_1") (pintype "passive"))
    )
    (net (code "15") (name "/CSI_D1_N") (class "Default")
      (node (ref "C4") (pin "1") (pinfunction "1_1") (pintype "passive"))
    )
    (net (code "16") (name "/CSI_D1_P") (class "Default")
      (node (ref "C3") (pin "1") (pinfunction "1_1") (pintype "passive"))
    )
    (net (code "17") (name "/CSI_D2_N") (class "Default")
      (node (ref "C6") (pin "1") (pinfunction "1_1") (pintype "passive"))
    )
    (net (code "18") (name "/CSI_D2_P") (class "Default")
      (node (ref "C5") (pin "1") (pinfunction "1_1") (pintype "passive"))
    )
    (net (code "19") (name "/CSI_D3_N") (class "Default")
      (node (ref "C10") (pin "1") (pinfunction "1_1") (pintype "passive"))
    )
    (net (code "20") (name "/CSI_D3_P") (class "Default")
      (node (ref "C9") (pin "1") (pinfunction "1_1") (pintype "passive"))
    )
    (net (code "21") (name "/DA0_N") (class "Default")
      (node (ref "C2") (pin "2") (pinfunction "2_2") (pintype "passive"))
      (node (ref "U1") (pin "32") (pinfunction "DA0N_32") (pintype "bidirectional"))
    )
    (net (code "22") (name "/DA0_P") (class "Default")
      (node (ref "C1") (pin "2") (pinfunction "2_2") (pintype "passive"))
      (node (ref "U1") (pin "31") (pinfunction "DA0P_31") (pintype "bidirectional"))
    )
    (net (code "23") (name "/DA1_N") (class "Default")
      (node (ref "C4") (pin "2") (pinfunction "2_2") (pintype "passive"))
      (node (ref "U1") (pin "36") (pinfunction "DA1N_36") (pintype "bidirectional"))
    )
    (net (code "24") (name "/DA1_P") (class "Default")
      (node (ref "C3") (pin "2") (pinfunction "2_2") (pintype "passive"))
      (node (ref "U1") (pin "35") (pinfunction "DA1P_35") (pintype "bidirectional"))
    )
    (net (code "25") (name "/DA2_N") (class "Default")
      (node (ref "C6") (pin "2") (pinfunction "2_2") (pintype "passive"))
      (node (ref "U1") (pin "38") (pinfunction "DA2N_38") (pintype "bidirectional"))
    )
    (net (code "26") (name "/DA2_P") (class "Default")
      (node (ref "C5") (pin "2") (pinfunction "2_2") (pintype "passive"))
      (node (ref "U1") (pin "37") (pinfunction "DA2P_37") (pintype "bidirectional"))
    )
    (net (code "27") (name "/DA3_N") (class "Default")
      (node (ref "C10") (pin "2") (pinfunction "2_2") (pintype "passive"))
      (node (ref "U1") (pin "42") (pinfunction "DA3N_42") (pintype "bidirectional"))
    )
    (net (code "28") (name "/DA3_P") (class "Default")
      (node (ref "C9") (pin "2") (pinfunction "2_2") (pintype "passive"))
      (node (ref "U1") (pin "41") (pinfunction "DA3P_41") (pintype "bidirectional"))
    )
    (net (code "29") (name "/PoC_A") (class "Default")
      (node (ref "C7") (pin "2") (pinfunction "2_2") (pintype "passive"))
      (node (ref "D22") (pin "1") (pinfunction "IO1_1") (pintype "bidirectional"))
      (node (ref "D22") (pin "10") (pinfunction "NC_10") (pintype "passive"))
      (node (ref "J2") (pin "3") (pinfunction "3_3") (pintype "passive"))
      (node (ref "L3") (pin "2") (pinfunction "2_2") (pintype "passive"))
    )
    (net (code "30") (name "/PoC_B") (class "Default")
      (node (ref "C8") (pin "2") (pinfunction "2_2") (pintype "passive"))
      (node (ref "D22") (pin "5") (pinfunction "IO4_5") (pintype "bidirectional"))
      (node (ref "D22") (pin "6") (pinfunction "NC_6") (pintype "passive"))
      (node (ref "D34") (pin "5") (pinfunction "IO4_5") (pintype "bidirectional"))
      (node (ref "D34") (pin "6") (pinfunction "NC_6") (pintype "passive"))
      (node (ref "J2") (pin "4") (pinfunction "4_4") (pintype "passive"))
      (node (ref "L5") (pin "2") (pinfunction "2_2") (pintype "passive"))
    )
    (net (code "31") (name "/PoC_C") (class "Default")
      (node (ref "C15") (pin "2") (pinfunction "2_2") (pintype "passive"))
      (node (ref "D23") (pin "1") (pinfunction "IO1_1") (pintype "bidirectional"))
      (node (ref "D23") (pin "10") (pinfunction "NC_10") (pintype "passive"))
      (node (ref "J2") (pin "1") (pinfunction "1_1") (pintype "passive"))
      (node (ref "L7") (pin "2") (pinfunction "2_2") (pintype "passive"))
    )
    (net (code "32") (name "/PoC_D") (class "Default")
      (node (ref "C16") (pin "2") (pinfunction "2_2") (pintype "passive"))
      (node (ref "D35") (pin "5") (pinfunction "IO4_5") (pintype "bidirectional"))
      (node (ref "D35") (pin "6") (pinfunction "NC_6") (pintype "passive"))
      (node (ref "J2") (pin "2") (pinfunction "2_2") (pintype "passive"))
      (node (ref "L9") (pin "2") (pinfunction "2_2") (pintype "passive"))
    )
    (net (code "33") (name "/PoC_PWR") (class "Default")
      (node (ref "C121") (pin "1") (pinfunction "1_1") (pintype "passive"))
      (node (ref "C122") (pin "1") (pinfunction "1_1") (pintype "passive"))
      (node (ref "C123") (pin "1") (pinfunction "1_1") (pintype "passive"))
      (node (ref "C124") (pin "1") (pinfunction "1_1") (pintype "passive"))
      (node (ref "L2") (pin "1") (pinfunction "1_1") (pintype "passive"))
      (node (ref "L4") (pin "1") (pinfunction "1_1") (pintype "passive"))
      (node (ref "L6") (pin "1") (pinfunction "1_1") (pintype "passive"))
      (node (ref "L8") (pin "1") (pinfunction "1_1") (pintype "passive"))
      (node (ref "R24") (pin "1") (pinfunction "1_1") (pintype "passive"))
      (node (ref "R26") (pin "1") (pinfunction "1_1") (pintype "passive"))
      (node (ref "R27") (pin "1") (pinfunction "1_1") (pintype "passive"))
      (node (ref "R29") (pin "1") (pinfunction "1_1") (pintype "passive"))
    )
    (net (code "34") (name "/SIOA_N") (class "Default")
      (node (ref "C12") (pin "1") (pinfunction "1_1") (pintype "passive"))
      (node (ref "U1") (pin "22") (pinfunction "SIOAN_22") (pintype "bidirectional"))
    )
    (net (code "35") (name "/SIOA_P") (class "Default")
      (node (ref "C7") (pin "1") (pinfunction "1_1") (pintype "passive"))
      (node (ref "U1") (pin "23") (pinfunction "SIOAP_23") (pintype "bidirectional"))
    )
    (net (code "36") (name "/SIOB_N") (class "Default")
      (node (ref "C13") (pin "1") (pinfunction "1_1") (pintype "passive"))
      (node (ref "U1") (pin "19") (pinfunction "SIOBN_19") (pintype "bidirectional"))
    )
    (net (code "37") (name "/SIOB_P") (class "Default")
      (node (ref "C8") (pin "1") (pinfunction "1_1") (pintype "passive"))
      (node (ref "U1") (pin "18") (pinfunction "SIOBP_18") (pintype "bidirectional"))
    )
    (net (code "38") (name "/SIOC_N") (class "Default")
      (node (ref "C17") (pin "1") (pinfunction "1_1") (pintype "passive"))
      (node (ref "U1") (pin "9") (pinfunction "SIOCN_9") (pintype "bidirectional"))
    )
    (net (code "39") (name "/SIOC_P") (class "Default")
      (node (ref "C15") (pin "1") (pinfunction "1_1") (pintype "passive"))
      (node (ref "U1") (pin "10") (pinfunction "SIOCP_10") (pintype "bidirectional"))
    )
    (net (code "40") (name "/SIOD_N") (class "Default")
      (node (ref "C18") (pin "1") (pinfunction "1_1") (pintype "passive"))
      (node (ref "U1") (pin "6") (pinfunction "SIODN_6") (pintype "bidirectional"))
    )
    (net (code "41") (name "/SIOD_P") (class "Default")
      (node (ref "C16") (pin "1") (pinfunction "1_1") (pintype "passive"))
      (node (ref "U1") (pin "5") (pinfunction "SIODP_5") (pintype "bidirectional"))
    )
    (net (code "42") (name "/X25_N") (class "Default")
      (node (ref "C20") (pin "1") (pinfunction "1_1") (pintype "passive"))
      (node (ref "U1") (pin "16") (pinfunction "X2_16") (pintype "passive"))
      (node (ref "Y1") (pin "3") (pinfunction "3_3") (pintype "passive"))
    )
    (net (code "43") (name "/X25_P") (class "Default")
      (node (ref "C19") (pin "1") (pinfunction "1_1") (pintype "passive"))
      (node (ref "U1") (pin "15") (pinfunction "X1/OSC_15") (pintype "passive"))
      (node (ref "Y1") (pin "1") (pinfunction "1_1") (pintype "passive"))
    )
    (net (code "44") (name "/XRES") (class "Default")
      (node (ref "R20") (pin "2") (pinfunction "2_2") (pintype "passive"))
      (node (ref "U1") (pin "17") (pinfunction "XRES_17") (pintype "passive"))
    )
    (net (code "45") (name "/nPWDN") (class "Default")
      (node (ref "R14") (pin "2") (pinfunction "2_2") (pintype "passive"))
    )
    (net (code "46") (name "2V_AUX") (class "Default")
      (node (ref "C42") (pin "2") (pinfunction "2_2") (pintype "passive"))
      (node (ref "C43") (pin "2") (pinfunction "2_2") (pintype "passive"))
      (node (ref "U2") (pin "3") (pinfunction "VIN_3") (pintype "power_in"))
      (node (ref "U3") (pin "3") (pinfunction "VIN_3") (pintype "power_in"))
    )
    (net (code "47") (name "3V3") (class "Default")
      (node (ref "C33") (pin "1") (pinfunction "1_1") (pintype "passive"))
      (node (ref "C34") (pin "2") (pinfunction "2_2") (pintype "passive"))
      (node (ref "R12") (pin "2") (pinfunction "2_2") (pintype "passive"))
      (node (ref "R13") (pin "2") (pinfunction "2_2") (pintype "passive"))
      (node (ref "R17") (pin "2") (pinfunction "2_2") (pintype "passive"))
      (node (ref "R21") (pin "2") (pinfunction "2_2") (pintype "passive"))
      (node (ref "R9") (pin "2") (pinfunction "2_2") (pintype "passive"))
      (node (ref "U1") (pin "24") (pinfunction "VDDIO_24") (pintype "power_in"))
    )
    (net (code "48") (name "GND") (class "Default")
      (node (ref "C121") (pin "2") (pinfunction "2_2") (pintype "passive"))
      (node (ref "C122") (pin "2") (pinfunction "2_2") (pintype "passive"))
      (node (ref "C123") (pin "2") (pinfunction "2_2") (pintype "passive"))
      (node (ref "C124") (pin "2") (pinfunction "2_2") (pintype "passive"))
      (node (ref "C19") (pin "2") (pinfunction "2_2") (pintype "passive"))
      (node (ref "C20") (pin "2") (pinfunction "2_2") (pintype "passive"))
      (node (ref "C21") (pin "2") (pinfunction "2_2") (pintype "passive"))
      (node (ref "C22") (pin "1") (pinfunction "1_1") (pintype "passive"))
      (node (ref "C23") (pin "2") (pinfunction "2_2") (pintype "passive"))
      (node (ref "C24") (pin "1") (pinfunction "1_1") (pintype "passive"))
      (node (ref "C25") (pin "2") (pinfunction "2_2") (pintype "passive"))
      (node (ref "C26") (pin "1") (pinfunction "1_1") (pintype "passive"))
      (node (ref "C27") (pin "2") (pinfunction "2_2") (pintype "passive"))
      (node (ref "C28") (pin "1") (pinfunction "1_1") (pintype "passive"))
      (node (ref "C29") (pin "2") (pinfunction "2_2") (pintype "passive"))
      (node (ref "C30") (pin "1") (pinfunction "1_1") (pintype "passive"))
      (node (ref "C31") (pin "2") (pinfunction "2_2") (pintype "passive"))
      (node (ref "C32") (pin "1") (pinfunction "1_1") (pintype "passive"))
      (node (ref "C33") (pin "2") (pinfunction "2_2") (pintype "passive"))
      (node (ref "C34") (pin "1") (pinfunction "1_1") (pintype "passive"))
      (node (ref "C35") (pin "2") (pinfunction "2_2") (pintype "passive"))
      (node (ref "C36") (pin "1") (pinfunction "1_1") (pintype "passive"))
      (node (ref "C40") (pin "2") (pinfunction "2_2") (pintype "passive"))
      (node (ref "C41") (pin "2") (pinfunction "2_2") (pintype "passive"))
      (node (ref "C42") (pin "1") (pinfunction "1_1") (pintype "passive"))
      (node (ref "C43") (pin "1") (pinfunction "1_1") (pintype "passive"))
      (node (ref "D22") (pin "3") (pinfunction "GND_3") (pintype "power_in"))
      (node (ref "D22") (pin "8") (pinfunction "GND_8") (pintype "power_in"))
      (node (ref "D23") (pin "3") (pinfunction "GND_3") (pintype "power_in"))
      (node (ref "D23") (pin "8") (pinfunction "GND_8") (pintype "power_in"))
      (node (ref "D34") (pin "3") (pinfunction "GND_3") (pintype "power_in"))
      (node (ref "D34") (pin "8") (pinfunction "GND_8") (pintype "power_in"))
      (node (ref "D35") (pin "3") (pinfunction "GND_3") (pintype "power_in"))
      (node (ref "D35") (pin "8") (pinfunction "GND_8") (pintype "power_in"))
      (node (ref "J2") (pin "MH1") (pinfunction "MH1_MH1") (pintype "passive"))
      (node (ref "J2") (pin "MH2") (pinfunction "MH2_MH2") (pintype "passive"))
      (node (ref "J2") (pin "MH3") (pinfunction "MH3_MH3") (pintype "passive"))
      (node (ref "J2") (pin "MH4") (pinfunction "MH4_MH4") (pintype "passive"))
      (node (ref "J2") (pin "MH5") (pinfunction "MH5_MH5") (pintype "passive"))
      (node (ref "R10") (pin "1") (pinfunction "1_1") (pintype "passive"))
      (node (ref "R11") (pin "1") (pinfunction "1_1") (pintype "passive"))
      (node (ref "R15") (pin "1") (pinfunction "1_1") (pintype "passive"))
      (node (ref "R16") (pin "1") (pinfunction "1_1") (pintype "passive"))
      (node (ref "R18") (pin "1") (pinfunction "1_1") (pintype "passive"))
      (node (ref "R19") (pin "1") (pinfunction "1_1") (pintype "passive"))
      (node (ref "R20") (pin "1") (pinfunction "1_1") (pintype "passive"))
      (node (ref "U1") (pin "57") (pinfunction "GND_57") (pintype "power_in"))
      (node (ref "U2") (pin "1") (pinfunction "GND_1") (pintype "power_in"))
      (node (ref "U3") (pin "1") (pinfunction "GND_1") (pintype "power_in"))
      (node (ref "Y1") (pin "2") (pinfunction "GND_2") (pintype "power_in"))
      (node (ref "Y1") (pin "4") (pinfunction "GND_4") (pintype "power_in"))
    )
    (net (code "49") (name "Net-(C12-Pad2)") (class "Default")
      (node (ref "C12") (pin "2") (pinfunction "2_2") (pintype "passive"))
      (node (ref "R10") (pin "2") (pinfunction "2_2") (pintype "passive"))
    )
    (net (code "50") (name "Net-(C13-Pad2)") (class "Default")
      (node (ref "C13") (pin "2") (pinfunction "2_2") (pintype "passive"))
      (node (ref "R11") (pin "2") (pinfunction "2_2") (pintype "passive"))
    )
    (net (code "51") (name "Net-(C17-Pad2)") (class "Default")
      (node (ref "C17") (pin "2") (pinfunction "2_2") (pintype "passive"))
      (node (ref "R18") (pin "2") (pinfunction "2_2") (pintype "passive"))
    )
    (net (code "52") (name "Net-(C18-Pad2)") (class "Default")
      (node (ref "C18") (pin "2") (pinfunction "2_2") (pintype "passive"))
      (node (ref "R19") (pin "2") (pinfunction "2_2") (pintype "passive"))
    )
    (net (code "53") (name "Net-(C21-Pad1)") (class "Default")
      (node (ref "C21") (pin "1") (pinfunction "1_1") (pintype "passive"))
      (node (ref "C22") (pin "2") (pinfunction "2_2") (pintype "passive"))
      (node (ref "U1") (pin "8") (pinfunction "CAP_VDD_8") (pintype "power_in"))
    )
    (net (code "54") (name "Net-(C23-Pad1)") (class "Default")
      (node (ref "C23") (pin "1") (pinfunction "1_1") (pintype "passive"))
      (node (ref "C24") (pin "2") (pinfunction "2_2") (pintype "passive"))
      (node (ref "U1") (pin "20") (pinfunction "CAP_VDD_20") (pintype "power_in"))
    )
    (net (code "55") (name "Net-(L2-Pad2)") (class "Default")
      (node (ref "L2") (pin "2") (pinfunction "2_2") (pintype "passive"))
      (node (ref "L3") (pin "1") (pinfunction "1_1") (pintype "passive"))
      (node (ref "R24") (pin "2") (pinfunction "2_2") (pintype "passive"))
    )
    (net (code "56") (name "Net-(L4-Pad2)") (class "Default")
      (node (ref "L4") (pin "2") (pinfunction "2_2") (pintype "passive"))
      (node (ref "L5") (pin "1") (pinfunction "1_1") (pintype "passive"))
      (node (ref "R26") (pin "2") (pinfunction "2_2") (pintype "passive"))
    )
    (net (code "57") (name "Net-(L6-Pad2)") (class "Default")
      (node (ref "L6") (pin "2") (pinfunction "2_2") (pintype "passive"))
      (node (ref "L7") (pin "1") (pinfunction "1_1") (pintype "passive"))
      (node (ref "R27") (pin "2") (pinfunction "2_2") (pintype "passive"))
    )
    (net (code "58") (name "Net-(L8-Pad2)") (class "Default")
      (node (ref "L8") (pin "2") (pinfunction "2_2") (pintype "passive"))
      (node (ref "L9") (pin "1") (pinfunction "1_1") (pintype "passive"))
      (node (ref "R29") (pin "2") (pinfunction "2_2") (pintype "passive"))
    )
    (net (code "59") (name "Net-(U1A-CFG0)") (class "Default")
      (node (ref "R13") (pin "1") (pinfunction "1_1") (pintype "passive"))
      (node (ref "R16") (pin "2") (pinfunction "2_2") (pintype "passive"))
      (node (ref "U1") (pin "4") (pinfunction "CFG0_4") (pintype "input"))
    )
    (net (code "60") (name "Net-(U1A-CFG1{slash}MFP6)") (class "Default")
      (node (ref "R12") (pin "1") (pinfunction "1_1") (pintype "passive"))
      (node (ref "R15") (pin "2") (pinfunction "2_2") (pintype "passive"))
      (node (ref "U1") (pin "25") (pinfunction "CFG1/MFP6_25") (pintype "bidirectional"))
    )
    (net (code "61") (name "Net-(U1A-PWDNB)") (class "Default")
      (node (ref "R14") (pin "1") (pinfunction "1_1") (pintype "passive"))
      (node (ref "R9") (pin "1") (pinfunction "1_1") (pintype "passive"))
      (node (ref "U1") (pin "11") (pinfunction "PWDNB_11") (pintype "input"))
    )
    (net (code "62") (name "unconnected-(D22-IO2-Pad2)") (class "Default")
      (node (ref "D22") (pin "2") (pinfunction "IO2_2") (pintype "bidirectional"))
    )
    (net (code "63") (name "unconnected-(D22-IO3-Pad4)") (class "Default")
      (node (ref "D22") (pin "4") (pinfunction "IO3_4") (pintype "bidirectional"))
    )
    (net (code "64") (name "unconnected-(D22-NC-Pad7)") (class "Default")
      (node (ref "D22") (pin "7") (pinfunction "NC_7") (pintype "passive"))
    )
    (net (code "65") (name "unconnected-(D22-NC-Pad9)") (class "Default")
      (node (ref "D22") (pin "9") (pinfunction "NC_9") (pintype "passive"))
    )
    (net (code "66") (name "unconnected-(D23-IO2-Pad2)") (class "Default")
      (node (ref "D23") (pin "2") (pinfunction "IO2_2") (pintype "bidirectional"))
    )
    (net (code "67") (name "unconnected-(D23-IO3-Pad4)") (class "Default")
      (node (ref "D23") (pin "4") (pinfunction "IO3_4") (pintype "bidirectional"))
    )
    (net (code "68") (name "unconnected-(D23-IO4-Pad5)") (class "Default")
      (node (ref "D23") (pin "5") (pinfunction "IO4_5") (pintype "bidirectional"))
    )
    (net (code "69") (name "unconnected-(D23-NC-Pad6)") (class "Default")
      (node (ref "D23") (pin "6") (pinfunction "NC_6") (pintype "passive"))
    )
    (net (code "70") (name "unconnected-(D23-NC-Pad7)") (class "Default")
      (node (ref "D23") (pin "7") (pinfunction "NC_7") (pintype "passive"))
    )
    (net (code "71") (name "unconnected-(D23-NC-Pad9)") (class "Default")
      (node (ref "D23") (pin "9") (pinfunction "NC_9") (pintype "passive"))
    )
    (net (code "72") (name "unconnected-(D34-IO1-Pad1)") (class "Default")
      (node (ref "D34") (pin "1") (pinfunction "IO1_1") (pintype "bidirectional"))
    )
    (net (code "73") (name "unconnected-(D34-IO2-Pad2)") (class "Default")
      (node (ref "D34") (pin "2") (pinfunction "IO2_2") (pintype "bidirectional"))
    )
    (net (code "74") (name "unconnected-(D34-IO3-Pad4)") (class "Default")
      (node (ref "D34") (pin "4") (pinfunction "IO3_4") (pintype "bidirectional"))
    )
    (net (code "75") (name "unconnected-(D34-NC-Pad7)") (class "Default")
      (node (ref "D34") (pin "7") (pinfunction "NC_7") (pintype "passive"))
    )
    (net (code "76") (name "unconnected-(D34-NC-Pad9)") (class "Default")
      (node (ref "D34") (pin "9") (pinfunction "NC_9") (pintype "passive"))
    )
    (net (code "77") (name "unconnected-(D34-NC-Pad10)") (class "Default")
      (node (ref "D34") (pin "10") (pinfunction "NC_10") (pintype "passive"))
    )
    (net (code "78") (name "unconnected-(D35-IO1-Pad1)") (class "Default")
      (node (ref "D35") (pin "1") (pinfunction "IO1_1") (pintype "bidirectional"))
    )
    (net (code "79") (name "unconnected-(D35-IO2-Pad2)") (class "Default")
      (node (ref "D35") (pin "2") (pinfunction "IO2_2") (pintype "bidirectional"))
    )
    (net (code "80") (name "unconnected-(D35-IO3-Pad4)") (class "Default")
      (node (ref "D35") (pin "4") (pinfunction "IO3_4") (pintype "bidirectional"))
    )
    (net (code "81") (name "unconnected-(D35-NC-Pad7)") (class "Default")
      (node (ref "D35") (pin "7") (pinfunction "NC_7") (pintype "passive"))
    )
    (net (code "82") (name "unconnected-(D35-NC-Pad9)") (class "Default")
      (node (ref "D35") (pin "9") (pinfunction "NC_9") (pintype "passive"))
    )
    (net (code "83") (name "unconnected-(D35-NC-Pad10)") (class "Default")
      (node (ref "D35") (pin "10") (pinfunction "NC_10") (pintype "passive"))
    )
    (net (code "84") (name "unconnected-(U1A-MFP0-Pad1)") (class "Default")
      (node (ref "U1") (pin "1") (pinfunction "MFP0_1") (pintype "bidirectional+no_connect"))
    )
    (net (code "85") (name "unconnected-(U1A-MFP1-Pad2)") (class "Default")
      (node (ref "U1") (pin "2") (pinfunction "MFP1_2") (pintype "bidirectional+no_connect"))
    )
    (net (code "86") (name "unconnected-(U1A-MFP2-Pad3)") (class "Default")
      (node (ref "U1") (pin "3") (pinfunction "MFP2_3") (pintype "bidirectional+no_connect"))
    )
    (net (code "87") (name "unconnected-(U1A-MFP3-Pad12)") (class "Default")
      (node (ref "U1") (pin "12") (pinfunction "MFP3_12") (pintype "bidirectional+no_connect"))
    )
    (net (code "88") (name "unconnected-(U1A-MFP4-Pad13)") (class "Default")
      (node (ref "U1") (pin "13") (pinfunction "MFP4_13") (pintype "bidirectional+no_connect"))
    )
    (net (code "89") (name "unconnected-(U1A-MFP5-Pad14)") (class "Default")
      (node (ref "U1") (pin "14") (pinfunction "MFP5_14") (pintype "bidirectional+no_connect"))
    )
    (net (code "90") (name "unconnected-(U1A-SCL1{slash}MFP8-Pad27)") (class "Default")
      (node (ref "U1") (pin "27") (pinfunction "SCL1/MFP8_27") (pintype "bidirectional+no_connect"))
    )
    (net (code "91") (name "unconnected-(U1A-SDA1{slash}MFP7-Pad26)") (class "Default")
      (node (ref "U1") (pin "26") (pinfunction "SDA1/MFP7_26") (pintype "bidirectional+no_connect"))
    )
    (net (code "92") (name "unconnected-(U1B-NC-Pad43)") (class "Default")
      (node (ref "U1") (pin "43") (pinfunction "NC_43") (pintype "passive+no_connect"))
    )
    (net (code "93") (name "unconnected-(U1B-NC-Pad44)") (class "Default")
      (node (ref "U1") (pin "44") (pinfunction "NC_44") (pintype "passive+no_connect"))
    )
    (net (code "94") (name "unconnected-(U1B-NC-Pad45)") (class "Default")
      (node (ref "U1") (pin "45") (pinfunction "NC_45") (pintype "passive+no_connect"))
    )
    (net (code "95") (name "unconnected-(U1B-NC-Pad46)") (class "Default")
      (node (ref "U1") (pin "46") (pinfunction "NC_46") (pintype "passive+no_connect"))
    )
    (net (code "96") (name "unconnected-(U1B-NC-Pad47)") (class "Default")
      (node (ref "U1") (pin "47") (pinfunction "NC_47") (pintype "passive+no_connect"))
    )
    (net (code "97") (name "unconnected-(U1B-NC-Pad48)") (class "Default")
      (node (ref "U1") (pin "48") (pinfunction "NC_48") (pintype "passive+no_connect"))
    )
    (net (code "98") (name "unconnected-(U1B-NC-Pad49)") (class "Default")
      (node (ref "U1") (pin "49") (pinfunction "NC_49") (pintype "passive+no_connect"))
    )
    (net (code "99") (name "unconnected-(U1B-NC-Pad50)") (class "Default")
      (node (ref "U1") (pin "50") (pinfunction "NC_50") (pintype "passive+no_connect"))
    )
    (net (code "100") (name "unconnected-(U1B-NC-Pad51)") (class "Default")
      (node (ref "U1") (pin "51") (pinfunction "NC_51") (pintype "passive+no_connect"))
    )
    (net (code "101") (name "unconnected-(U1B-NC-Pad52)") (class "Default")
      (node (ref "U1") (pin "52") (pinfunction "NC_52") (pintype "passive+no_connect"))
    )
    (net (code "102") (name "unconnected-(U1B-NC-Pad53)") (class "Default")
      (node (ref "U1") (pin "53") (pinfunction "NC_53") (pintype "passive+no_connect"))
    )
    (net (code "103") (name "unconnected-(U1B-NC-Pad54)") (class "Default")
      (node (ref "U1") (pin "54") (pinfunction "NC_54") (pintype "passive+no_connect"))
    )
  )
)
